# piTCx-Power-HAT.net
KiCad netlist of a schematic drawn in EAGLE
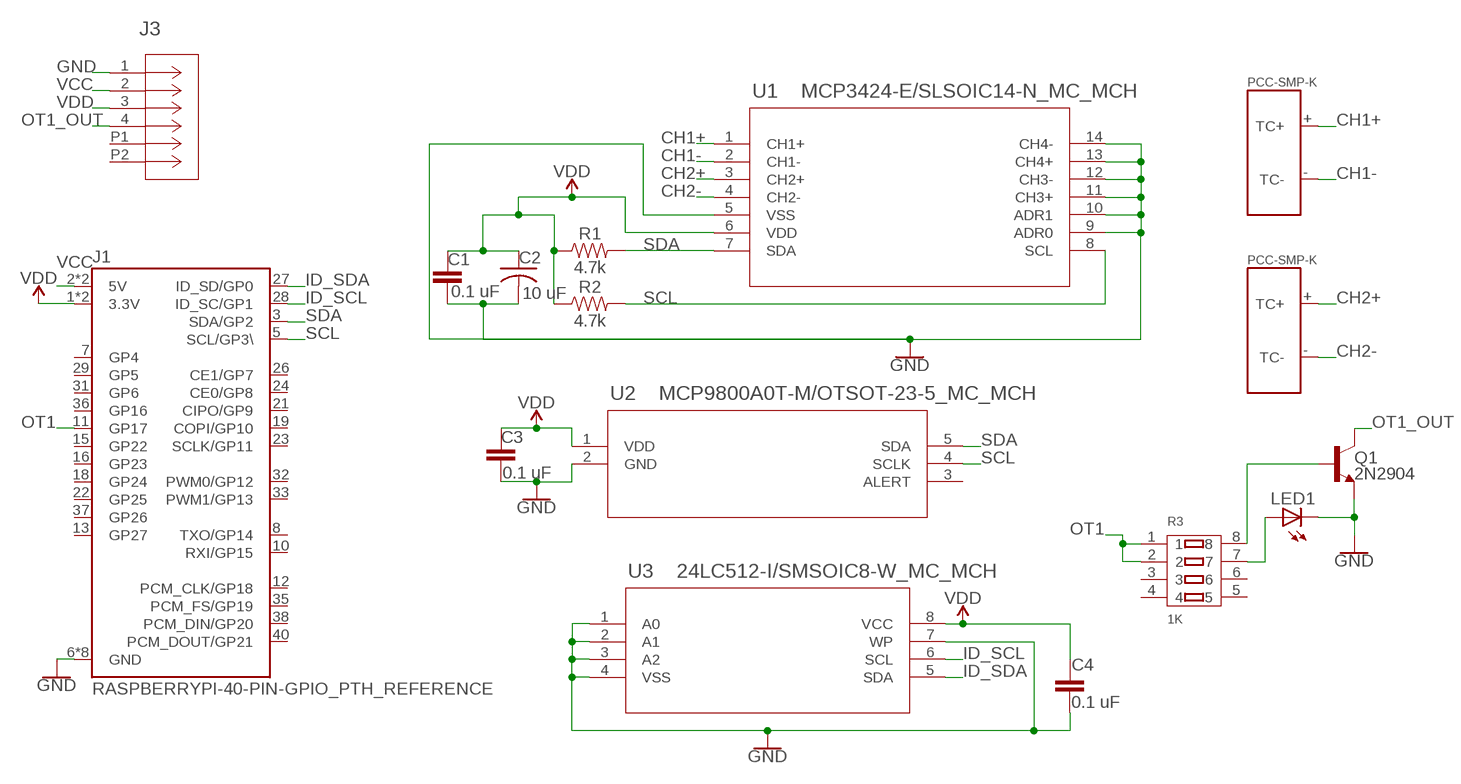
[diagram p0: schematic, sheet 1]

(export (version "E")
  (design (tool "Eeschema 10.0.6"))
  (components
    (comp (ref "C1")
      (value "0.1 uF")
      (footprint "eagle-import:CAP_0805")
      (fields
        (field (name "DIGIKEY_PART_NUMBER") "311-1140-2-ND")
        (field (name "MANUFACTURER") "Yageo")
        (field (name "MPN") "CC0805KRX7R9BB104")
        (field (name "CREATED_BY") "PCBLayout.com")
      )
      (libsource (lib "eagle-import") (part "CC0805KRX7R9BB104"))
    )
    (comp (ref "C2")
      (value "10 uF")
      (footprint "eagle-import:CAP_TANT_B")
      (fields
        (field (name "DIGIKEY_PART_NUMBER") "478-1673-2-ND")
        (field (name "MANUFACTURER") "AVX Corporation")
        (field (name "MPN") "TAJB106K016RNJ")
        (field (name "MPN_1") "T494A106M020AT")
        (field (name "CREATED_BY") "PCBLayout.com")
      )
      (libsource (lib "eagle-import") (part "TAJB106K016RNJ"))
    )
    (comp (ref "C3")
      (value "0.1 uF")
      (footprint "eagle-import:CAP_0805")
      (fields
        (field (name "DIGIKEY_PART_NUMBER") "311-1140-2-ND")
        (field (name "MANUFACTURER") "Yageo")
        (field (name "MPN") "CC0805KRX7R9BB104")
        (field (name "CREATED_BY") "PCBLayout.com")
      )
      (libsource (lib "eagle-import") (part "CC0805KRX7R9BB104"))
    )
    (comp (ref "C4")
      (value "0.1 uF")
      (footprint "eagle-import:CAP_0805")
      (fields
        (field (name "DIGIKEY_PART_NUMBER") "311-1140-2-ND")
        (field (name "MANUFACTURER") "Yageo")
        (field (name "MPN") "CC0805KRX7R9BB104")
        (field (name "CREATED_BY") "PCBLayout.com")
      )
      (libsource (lib "eagle-import") (part "CC0805KRX7R9BB104"))
    )
    (comp (ref "J1")
      (value "RASPBERRYPI-40-PIN-GPIO_PTH_REFERENCE")
      (footprint "eagle-import:RASPBERRY_PI_HAT_40_PIN_PTH_WITH_REFERNCE")
      (libsource (lib "eagle-import") (part "RASPBERRYPI-40-PIN-GPIO_PTH_REFERENCE"))
    )
    (comp (ref "J3")
      (value "436500414CON_436500414")
      (footprint "eagle-import:CON_436500414")
      (fields
        (field (name "MANUFACTURER_PART_NUMBER") "436500414")
        (field (name "COPYRIGHT") "Copyright (C) 2024 Ultra Librarian. All rights reserved.")
      )
      (libsource (lib "eagle-import") (part "436500414CON_436500414"))
    )
    (comp (ref "LED1")
      (value "LEDCHIP-LED0805")
      (footprint "eagle-import:CHIP-LED0805")
      (libsource (lib "eagle-import") (part "LEDCHIP-LED0805"))
    )
    (comp (ref "Q1")
      (value "2N2904")
      (footprint "eagle-import:SOT23-3")
      (libsource (lib "eagle-import") (part "TRANS_NPN-MMBTA42"))
    )
    (comp (ref "R1")
      (value "4.7k")
      (footprint "eagle-import:0603")
      (libsource (lib "eagle-import") (part "4.7KOHM-0603-1/10W-1%"))
    )
    (comp (ref "R2")
      (value "4.7k")
      (footprint "eagle-import:0603")
      (libsource (lib "eagle-import") (part "4.7KOHM-0603-1/10W-1%"))
    )
    (comp (ref "R3")
      (value "1K")
      (footprint "eagle-import:RA1206-8")
      (fields (field (name "MPN") "Chip-Array-Series-1%"))
      (libsource (lib "eagle-import") (part "SMD-RES-ARRAY-1K-4R(RA1206-8)"))
    )
    (comp (ref "U$1")
      (value "THERMOCOUPLECONN-PCC-SMP-K")
      (footprint "eagle-import:THERMOCOUPLECONN-PCC-SMP-K")
      (libsource (lib "eagle-import") (part "THERMOCOUPLECONN-PCC-SMP-K"))
    )
    (comp (ref "U$2")
      (value "THERMOCOUPLECONN-PCC-SMP-K")
      (footprint "eagle-import:THERMOCOUPLECONN-PCC-SMP-K")
      (libsource (lib "eagle-import") (part "THERMOCOUPLECONN-PCC-SMP-K"))
    )
    (comp (ref "U1")
      (value "MCP3424-E/SLSOIC14-N_MC_MCH")
      (footprint "eagle-import:SOIC14-N_MC_MCH")
      (fields
        (field (name "MANUFACTURER_PART_NUMBER") "MCP3424-E/SL")
        (field (name "COPYRIGHT") "Copyright (C) 2023 Ultra Librarian. All rights reserved.")
      )
      (libsource (lib "eagle-import") (part "MCP3424-E/SLSOIC14-N_MC_MCH"))
    )
    (comp (ref "U2")
      (value "MCP9800A0T-M/OTSOT-23-5_MC_MCH")
      (footprint "eagle-import:SOT-23-5_MC_MCH")
      (fields
        (field (name "MANUFACTURER_PART_NUMBER") "MCP9800A0T-M/OT")
        (field (name "COPYRIGHT") "Copyright (C) 2023 Ultra Librarian. All rights reserved.")
      )
      (libsource (lib "eagle-import") (part "MCP9800A0T-M/OTSOT-23-5_MC_MCH"))
    )
    (comp (ref "U3")
      (value "24LC512-I/SMSOIC8-W_MC_MCH")
      (footprint "eagle-import:SOIC8-W_MC_MCH")
      (fields
        (field (name "MANUFACTURER_PART_NUMBER") "24LC512-I/SM")
        (field (name "COPYRIGHT") "Copyright (C) 2023 Ultra Librarian. All rights reserved.")
      )
      (libsource (lib "eagle-import") (part "24LC512-I/SMSOIC8-W_MC_MCH"))
    )
  )
  (nets
    (net (code "1") (name "/CH1+") (class "Default")
      (node (ref "U$1") (pin "+") (pinfunction "TC+_+") (pintype "bidirectional"))
      (node (ref "U1") (pin "1") (pinfunction "CH1+_1") (pintype "input"))
    )
    (net (code "2") (name "/CH1-") (class "Default")
      (node (ref "U$1") (pin "-") (pinfunction "TC-_-") (pintype "bidirectional"))
      (node (ref "U1") (pin "2") (pinfunction "CH1-_2") (pintype "input"))
    )
    (net (code "3") (name "/CH2+") (class "Default")
      (node (ref "U$2") (pin "+") (pinfunction "TC+_+") (pintype "bidirectional"))
      (node (ref "U1") (pin "3") (pinfunction "CH2+_3") (pintype "input"))
    )
    (net (code "4") (name "/CH2-") (class "Default")
      (node (ref "U$2") (pin "-") (pinfunction "TC-_-") (pintype "bidirectional"))
      (node (ref "U1") (pin "4") (pinfunction "CH2-_4") (pintype "input"))
    )
    (net (code "5") (name "/ID_SCL") (class "Default")
      (node (ref "J1") (pin "28") (pinfunction "ID_SC/GP1_28") (pintype "bidirectional"))
      (node (ref "U3") (pin "6") (pinfunction "SCL_6") (pintype "input"))
    )
    (net (code "6") (name "/ID_SDA") (class "Default")
      (node (ref "J1") (pin "27") (pinfunction "ID_SD/GP0_27") (pintype "bidirectional"))
      (node (ref "U3") (pin "5") (pinfunction "SDA_5") (pintype "bidirectional"))
    )
    (net (code "7") (name "/OT1") (class "Default")
      (node (ref "J1") (pin "11") (pinfunction "GP17_11") (pintype "bidirectional"))
      (node (ref "R3") (pin "1") (pinfunction "1_1") (pintype "bidirectional"))
      (node (ref "R3") (pin "2") (pinfunction "2_2") (pintype "bidirectional"))
    )
    (net (code "8") (name "/OT1_OUT") (class "Default")
      (node (ref "J3") (pin "4") (pinfunction "4_4") (pintype "passive"))
      (node (ref "Q1") (pin "3") (pinfunction "C_3") (pintype "passive"))
    )
    (net (code "9") (name "/SCL") (class "Default")
      (node (ref "J1") (pin "5") (pinfunction "SCL/GP3\\_5") (pintype "bidirectional"))
      (node (ref "R2") (pin "2") (pinfunction "2_2") (pintype "passive"))
      (node (ref "U1") (pin "8") (pinfunction "SCL_8") (pintype "input"))
      (node (ref "U2") (pin "4") (pinfunction "SCLK_4") (pintype "passive"))
    )
    (net (code "10") (name "/SDA") (class "Default")
      (node (ref "J1") (pin "3") (pinfunction "SDA/GP2_3") (pintype "bidirectional"))
      (node (ref "R1") (pin "2") (pinfunction "2_2") (pintype "passive"))
      (node (ref "U1") (pin "7") (pinfunction "SDA_7") (pintype "bidirectional"))
      (node (ref "U2") (pin "5") (pinfunction "SDA_5") (pintype "passive"))
    )
    (net (code "11") (name "/VCC") (class "Default")
      (node (ref "J1") (pin "2") (pinfunction "5V_2") (pintype "power_in"))
      (node (ref "J1") (pin "4") (pinfunction "5V_4") (pintype "power_in"))
      (node (ref "J3") (pin "2") (pinfunction "2_2") (pintype "passive"))
    )
    (net (code "12") (name "GND") (class "Default")
      (node (ref "C1") (pin "2") (pinfunction "2_2") (pintype "passive"))
      (node (ref "C2") (pin "2") (pinfunction "2_2") (pintype "passive"))
      (node (ref "C3") (pin "2") (pinfunction "2_2") (pintype "passive"))
      (node (ref "C4") (pin "2") (pinfunction "2_2") (pintype "passive"))
      (node (ref "J1") (pin "14") (pinfunction "GND_14") (pintype "power_in"))
      (node (ref "J1") (pin "20") (pinfunction "GND_20") (pintype "power_in"))
      (node (ref "J1") (pin "25") (pinfunction "GND_25") (pintype "power_in"))
      (node (ref "J1") (pin "30") (pinfunction "GND_30") (pintype "power_in"))
      (node (ref "J1") (pin "34") (pinfunction "GND_34") (pintype "power_in"))
      (node (ref "J1") (pin "39") (pinfunction "GND_39") (pintype "power_in"))
      (node (ref "J1") (pin "6") (pinfunction "GND_6") (pintype "power_in"))
      (node (ref "J1") (pin "9") (pinfunction "GND_9") (pintype "power_in"))
      (node (ref "J3") (pin "1") (pinfunction "1_1") (pintype "passive"))
      (node (ref "LED1") (pin "C") (pinfunction "C_C") (pintype "passive"))
      (node (ref "Q1") (pin "2") (pinfunction "E_2") (pintype "passive"))
      (node (ref "U1") (pin "10") (pinfunction "ADR1_10") (pintype "passive"))
      (node (ref "U1") (pin "11") (pinfunction "CH3+_11") (pintype "input"))
      (node (ref "U1") (pin "12") (pinfunction "CH3-_12") (pintype "input"))
      (node (ref "U1") (pin "13") (pinfunction "CH4+_13") (pintype "input"))
      (node (ref "U1") (pin "14") (pinfunction "CH4-_14") (pintype "input"))
      (node (ref "U1") (pin "5") (pinfunction "VSS_5") (pintype "power_in"))
      (node (ref "U1") (pin "9") (pinfunction "ADR0_9") (pintype "passive"))
      (node (ref "U2") (pin "2") (pinfunction "GND_2") (pintype "passive"))
      (node (ref "U3") (pin "1") (pinfunction "A0_1") (pintype "input"))
      (node (ref "U3") (pin "2") (pinfunction "A1_2") (pintype "input"))
      (node (ref "U3") (pin "3") (pinfunction "A2_3") (pintype "input"))
      (node (ref "U3") (pin "4") (pinfunction "VSS_4") (pintype "passive"))
      (node (ref "U3") (pin "7") (pinfunction "WP_7") (pintype "input"))
    )
    (net (code "13") (name "Net-(LED1-PadA)") (class "Default")
      (node (ref "LED1") (pin "A") (pinfunction "A_A") (pintype "passive"))
      (node (ref "R3") (pin "7") (pinfunction "7_7") (pintype "bidirectional"))
    )
    (net (code "14") (name "Net-(Q1-B)") (class "Default")
      (node (ref "Q1") (pin "1") (pinfunction "B_1") (pintype "passive"))
      (node (ref "R3") (pin "8") (pinfunction "8_8") (pintype "bidirectional"))
    )
    (net (code "15") (name "VDD") (class "Default")
      (node (ref "C1") (pin "1") (pinfunction "1_1") (pintype "passive"))
      (node (ref "C2") (pin "1") (pinfunction "1_1") (pintype "passive"))
      (node (ref "C3") (pin "1") (pinfunction "1_1") (pintype "passive"))
      (node (ref "C4") (pin "1") (pinfunction "1_1") (pintype "passive"))
      (node (ref "J1") (pin "1") (pinfunction "3.3V_1") (pintype "power_in"))
      (node (ref "J1") (pin "17") (pinfunction "3.3V_17") (pintype "power_in"))
      (node (ref "J3") (pin "3") (pinfunction "3_3") (pintype "passive"))
      (node (ref "R1") (pin "1") (pinfunction "1_1") (pintype "passive"))
      (node (ref "R2") (pin "1") (pinfunction "1_1") (pintype "passive"))
      (node (ref "U1") (pin "6") (pinfunction "VDD_6") (pintype "power_in"))
      (node (ref "U2") (pin "1") (pinfunction "VDD_1") (pintype "passive"))
      (node (ref "U3") (pin "8") (pinfunction "VCC_8") (pintype "passive"))
    )
    (net (code "16") (name "unconnected-(J1-CE0{slash}GP8-Pad24)") (class "Default")
      (node (ref "J1") (pin "24") (pinfunction "CE0/GP8_24") (pintype "output"))
    )
    (net (code "17") (name "unconnected-(J1-CE1{slash}GP7-Pad26)") (class "Default")
      (node (ref "J1") (pin "26") (pinfunction "CE1/GP7_26") (pintype "output"))
    )
    (net (code "18") (name "unconnected-(J1-CIPO{slash}GP9-Pad21)") (class "Default")
      (node (ref "J1") (pin "21") (pinfunction "CIPO/GP9_21") (pintype "input"))
    )
    (net (code "19") (name "unconnected-(J1-COPI{slash}GP10-Pad19)") (class "Default")
      (node (ref "J1") (pin "19") (pinfunction "COPI/GP10_19") (pintype "output"))
    )
    (net (code "20") (name "unconnected-(J1-GP4-Pad7)") (class "Default")
      (node (ref "J1") (pin "7") (pinfunction "GP4_7") (pintype "bidirectional"))
    )
    (net (code "21") (name "unconnected-(J1-GP5-Pad29)") (class "Default")
      (node (ref "J1") (pin "29") (pinfunction "GP5_29") (pintype "bidirectional"))
    )
    (net (code "22") (name "unconnected-(J1-GP6-Pad31)") (class "Default")
      (node (ref "J1") (pin "31") (pinfunction "GP6_31") (pintype "bidirectional"))
    )
    (net (code "23") (name "unconnected-(J1-GP16-Pad36)") (class "Default")
      (node (ref "J1") (pin "36") (pinfunction "GP16_36") (pintype "bidirectional"))
    )
    (net (code "24") (name "unconnected-(J1-GP22-Pad15)") (class "Default")
      (node (ref "J1") (pin "15") (pinfunction "GP22_15") (pintype "bidirectional"))
    )
    (net (code "25") (name "unconnected-(J1-GP23-Pad16)") (class "Default")
      (node (ref "J1") (pin "16") (pinfunction "GP23_16") (pintype "bidirectional"))
    )
    (net (code "26") (name "unconnected-(J1-GP24-Pad18)") (class "Default")
      (node (ref "J1") (pin "18") (pinfunction "GP24_18") (pintype "bidirectional"))
    )
    (net (code "27") (name "unconnected-(J1-GP25-Pad22)") (class "Default")
      (node (ref "J1") (pin "22") (pinfunction "GP25_22") (pintype "bidirectional"))
    )
    (net (code "28") (name "unconnected-(J1-GP26-Pad37)") (class "Default")
      (node (ref "J1") (pin "37") (pinfunction "GP26_37") (pintype "bidirectional"))
    )
    (net (code "29") (name "unconnected-(J1-GP27-Pad13)") (class "Default")
      (node (ref "J1") (pin "13") (pinfunction "GP27_13") (pintype "bidirectional"))
    )
    (net (code "30") (name "unconnected-(J1-PCM_CLK{slash}GP18-Pad12)") (class "Default")
      (node (ref "J1") (pin "12") (pinfunction "PCM_CLK/GP18_12") (pintype "bidirectional"))
    )
    (net (code "31") (name "unconnected-(J1-PCM_DIN{slash}GP20-Pad38)") (class "Default")
      (node (ref "J1") (pin "38") (pinfunction "PCM_DIN/GP20_38") (pintype "bidirectional"))
    )
    (net (code "32") (name "unconnected-(J1-PCM_DOUT{slash}GP21-Pad40)") (class "Default")
      (node (ref "J1") (pin "40") (pinfunction "PCM_DOUT/GP21_40") (pintype "bidirectional"))
    )
    (net (code "33") (name "unconnected-(J1-PCM_FS{slash}GP19-Pad35)") (class "Default")
      (node (ref "J1") (pin "35") (pinfunction "PCM_FS/GP19_35") (pintype "bidirectional"))
    )
    (net (code "34") (name "unconnected-(J1-PWM0{slash}GP12-Pad32)") (class "Default")
      (node (ref "J1") (pin "32") (pinfunction "PWM0/GP12_32") (pintype "bidirectional"))
    )
    (net (code "35") (name "unconnected-(J1-PWM1{slash}GP13-Pad33)") (class "Default")
      (node (ref "J1") (pin "33") (pinfunction "PWM1/GP13_33") (pintype "bidirectional"))
    )
    (net (code "36") (name "unconnected-(J1-RXI{slash}GP15-Pad10)") (class "Default")
      (node (ref "J1") (pin "10") (pinfunction "RXI/GP15_10") (pintype "input"))
    )
    (net (code "37") (name "unconnected-(J1-SCLK{slash}GP11-Pad23)") (class "Default")
      (node (ref "J1") (pin "23") (pinfunction "SCLK/GP11_23") (pintype "output"))
    )
    (net (code "38") (name "unconnected-(J1-TXO{slash}GP14-Pad8)") (class "Default")
      (node (ref "J1") (pin "8") (pinfunction "TXO/GP14_8") (pintype "output"))
    )
    (net (code "39") (name "unconnected-(J3-PadP1)") (class "Default")
      (node (ref "J3") (pin "P1") (pinfunction "P1_P1") (pintype "passive"))
    )
    (net (code "40") (name "unconnected-(J3-PadP2)") (class "Default")
      (node (ref "J3") (pin "P2") (pinfunction "P2_P2") (pintype "passive"))
    )
    (net (code "41") (name "unconnected-(R3-Pad3)") (class "Default")
      (node (ref "R3") (pin "3") (pinfunction "3_3") (pintype "bidirectional"))
    )
    (net (code "42") (name "unconnected-(R3-Pad4)") (class "Default")
      (node (ref "R3") (pin "4") (pinfunction "4_4") (pintype "bidirectional"))
    )
    (net (code "43") (name "unconnected-(R3-Pad5)") (class "Default")
      (node (ref "R3") (pin "5") (pinfunction "5_5") (pintype "bidirectional"))
    )
    (net (code "44") (name "unconnected-(R3-Pad6)") (class "Default")
      (node (ref "R3") (pin "6") (pinfunction "6_6") (pintype "bidirectional"))
    )
    (net (code "45") (name "unconnected-(U2-ALERT-Pad3)") (class "Default")
      (node (ref "U2") (pin "3") (pinfunction "ALERT_3") (pintype "passive"))
    )
  )
)
